# phase_current_sense.net
KiCad netlist of a schematic drawn in Altium Designer
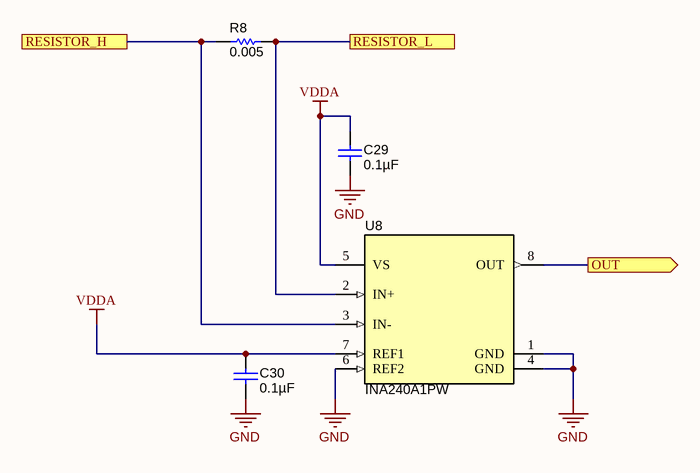
[diagram p0: phase_current_sense.SchDoc]

(export (version "E")
  (design (tool "Eeschema 10.0.6"))
  (components
    (comp (ref "C29")
      (value "GCM155R71C104KA55D")
      (footprint "CAP_0402")
      (description "CAP, CERM, 0.1 µF, 16 V, +/- 10%, X7R, 0402")
      (fields
        (field (name "VALUEDISPLAYED") "0.1µF")
        (field (name "MANUFACTURER") "MuRata")
        (field (name "PUBLISHER") "Texas Instruments")
      )
      (libsource (lib "Capacitor_Ceramic") (part "GCM155R71C104KA55D"))
    )
    (comp (ref "C30")
      (value "GCM155R71C104KA55D")
      (footprint "CAP_0402")
      (description "CAP, CERM, 0.1 µF, 16 V, +/- 10%, X7R, 0402")
      (fields
        (field (name "VALUEDISPLAYED") "0.1µF")
        (field (name "MANUFACTURER") "MuRata")
        (field (name "PUBLISHER") "Texas Instruments")
      )
      (libsource (lib "Capacitor_Ceramic") (part "GCM155R71C104KA55D"))
    )
    (comp (ref "R8")
      (value "CRE2512-FZ-R005E-3")
      (footprint "CRE2512-R5_R9")
      (description "RES, 0.005, 1%, 3 W, AEC-Q200 Grade 0, 2512")
      (fields
        (field (name "VALUEDISPLAYED") "0.005")
        (field (name "MANUFACTURER") "Bourns")
        (field (name "PUBLISHER") "Texas Instruments")
      )
      (libsource (lib "Resistor_2512") (part "CRE2512-FZ-R005E-3"))
    )
    (comp (ref "U8")
      (value "INA240A1PW")
      (footprint "PW0008A_N")
      (fields
        (field (name "MANUFACTURER") "Texas Instruments")
        (field (name "SYMBOLCREATOR") "Altium")
        (field (name "PUBLISHER") "Texas Instruments")
      )
      (libsource (lib "TI_Pre_RTM") (part "INA240A1PW"))
    )
  )
  (nets
    (net (code "1") (name "/OUT") (class "Default")
      (node (ref "U8") (pin "8") (pinfunction "OUT_8") (pintype "output"))
    )
    (net (code "2") (name "/RESISTOR_H") (class "Default")
      (node (ref "R8") (pin "1") (pinfunction "1_1") (pintype "passive"))
      (node (ref "U8") (pin "3") (pinfunction "IN-_3") (pintype "input"))
    )
    (net (code "3") (name "/RESISTOR_L") (class "Default")
      (node (ref "R8") (pin "2") (pinfunction "2_2") (pintype "passive"))
      (node (ref "U8") (pin "2") (pinfunction "IN+_2") (pintype "input"))
    )
    (net (code "4") (name "GND") (class "Default")
      (node (ref "C29") (pin "1") (pinfunction "1_1") (pintype "passive"))
      (node (ref "C30") (pin "1") (pinfunction "1_1") (pintype "passive"))
      (node (ref "U8") (pin "1") (pinfunction "GND_1") (pintype "power_in"))
      (node (ref "U8") (pin "4") (pinfunction "GND_4") (pintype "power_in"))
      (node (ref "U8") (pin "6") (pinfunction "REF2_6") (pintype "input"))
    )
    (net (code "5") (name "VDDA") (class "Default")
      (node (ref "C29") (pin "2") (pinfunction "2_2") (pintype "passive"))
      (node (ref "C30") (pin "2") (pinfunction "2_2") (pintype "passive"))
      (node (ref "U8") (pin "5") (pinfunction "VS_5") (pintype "power_in"))
      (node (ref "U8") (pin "7") (pinfunction "REF1_7") (pintype "input"))
    )
  )
)
